# input-device.net
KiCad netlist of a schematic drawn in EAGLE
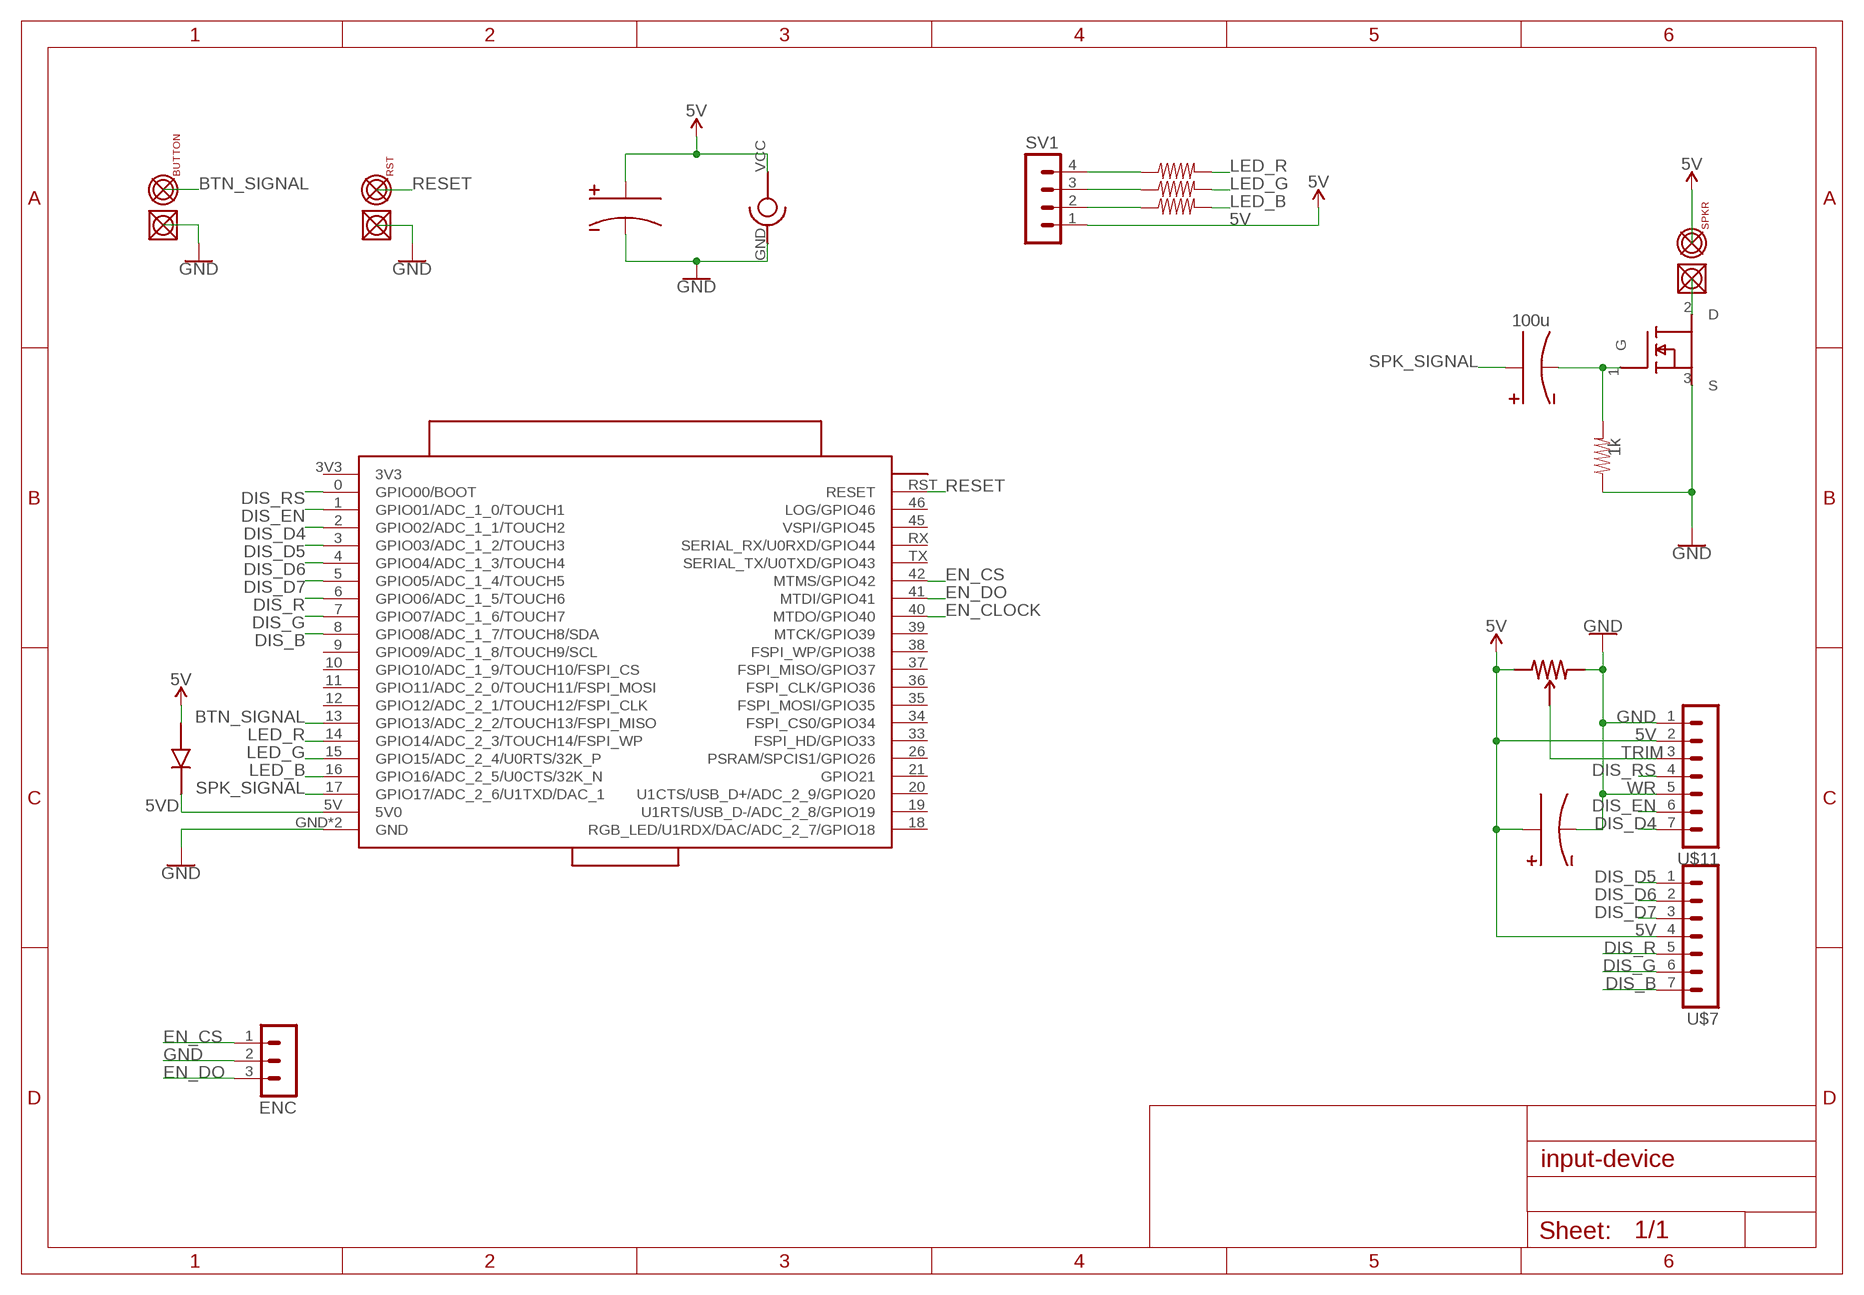
[diagram p0: schematic, sheet 1]

(export (version "E")
  (design (tool "Eeschema 10.0.6"))
  (components
    (comp (ref "BUTTON")
      (value "PIN-HEADER-02X1GROUND")
      (footprint "eagle-import:02X1-PAD-2.54PITCH-MASK-NAME")
      (libsource (lib "eagle-import") (part "PIN-HEADER-02X1GROUND"))
    )
    (comp (ref "ENC")
      (value "PIN-HEADER-03X1THRU-254")
      (footprint "eagle-import:MA03-1")
      (libsource (lib "eagle-import") (part "PIN-HEADER-03X1THRU-254"))
    )
    (comp (ref "IRL540NPBF")
      (value "MOSFET-N-IRL540NPBFBENDED-SHORTEST")
      (footprint "eagle-import:TO220AH-SHORTEST-BEND")
      (libsource (lib "eagle-import") (part "MOSFET-N-IRL540NPBFBENDED-SHORTEST"))
    )
    (comp (ref "R")
      (value "1k")
      (footprint "eagle-import:RESISTOR-THRU-1_4")
      (fields (field (name "R1") "1k"))
      (libsource (lib "eagle-import") (part "RESISTOR"))
    )
    (comp (ref "RST")
      (value "PIN-HEADER-02X1GROUND")
      (footprint "eagle-import:02X1-PAD-2.54PITCH-MASK-NAME")
      (libsource (lib "eagle-import") (part "PIN-HEADER-02X1GROUND"))
    )
    (comp (ref "SPKR")
      (value "PIN-HEADER-02X1GROUND")
      (footprint "eagle-import:02X1-PAD-2.54PITCH-MASK-NAME")
      (libsource (lib "eagle-import") (part "PIN-HEADER-02X1GROUND"))
    )
    (comp (ref "SV1")
      (value "PIN-HEADER-04X01")
      (footprint "eagle-import:MA04-1")
      (libsource (lib "eagle-import") (part "PIN-HEADER-04X01"))
    )
    (comp (ref "U$1")
      (value "RESISTOR")
      (footprint "eagle-import:RESISTOR-THRU-1_4")
      (libsource (lib "eagle-import") (part "RESISTOR"))
    )
    (comp (ref "U$2")
      (value "POWER-JACK")
      (footprint "eagle-import:JACK-5.5X2.1-THRU")
      (libsource (lib "eagle-import") (part "POWER-JACK"))
    )
    (comp (ref "U$3")
      (value "ESP32-S2-SAOLA-1")
      (footprint "eagle-import:ESP32-S2-SAOLA-1")
      (libsource (lib "eagle-import") (part "ESP32-S2-SAOLA-1"))
    )
    (comp (ref "U$4")
      (value "RESISTOR")
      (footprint "eagle-import:RESISTOR-THRU-1_4")
      (libsource (lib "eagle-import") (part "RESISTOR"))
    )
    (comp (ref "U$5")
      (value "100")
      (footprint "eagle-import:RESISTOR-THRU-1_4")
      (libsource (lib "eagle-import") (part "RESISTOR"))
    )
    (comp (ref "U$6")
      (value "CAPACITOR-POLARIZEDCAP-DIAM-8.3MM-H-12MM-BENT")
      (footprint "eagle-import:CAP-DIAM-8.3MM-H-12MM-BENT")
      (libsource (lib "eagle-import") (part "CAPACITOR-POLARIZEDCAP-DIAM-8.3MM-H-12MM-BENT"))
    )
    (comp (ref "U$7")
      (value "PIN-HEADER-07X1")
      (footprint "eagle-import:MA07-1")
      (libsource (lib "eagle-import") (part "PIN-HEADER-07X1"))
    )
    (comp (ref "U$8")
      (value "DIODE")
      (footprint "eagle-import:DIODE")
      (libsource (lib "eagle-import") (part "DIODE"))
    )
    (comp (ref "U$9")
      (value "TRIMMER")
      (footprint "eagle-import:TRIMMER-PLASTIC-BLUE-9MM-2,54")
      (libsource (lib "eagle-import") (part "TRIMMER"))
    )
    (comp (ref "U$11")
      (value "PIN-HEADER-07X1")
      (footprint "eagle-import:MA07-1")
      (libsource (lib "eagle-import") (part "PIN-HEADER-07X1"))
    )
    (comp (ref "U$13")
      (value "CAPACITOR-POLARIZEDCAP-DIAM-8.3MM-H-12MM-BENT")
      (footprint "eagle-import:CAP-DIAM-8.3MM-H-12MM-BENT")
      (libsource (lib "eagle-import") (part "CAPACITOR-POLARIZEDCAP-DIAM-8.3MM-H-12MM-BENT"))
    )
    (comp (ref "U$14")
      (value "100u")
      (footprint "eagle-import:CAP-DIAM-6.5MM-H-11.3MM-BENT-FLIP")
      (fields (field (name "C1") "100u"))
      (libsource (lib "eagle-import") (part "CAPACITOR-POLARIZEDCAP-DIAM-6.5MM-H11.3MM-BENT-FLIP"))
    )
  )
  (nets
    (net (code "1") (name "/5VD") (class "Default")
      (node (ref "U$3") (pin "5V") (pinfunction "5V0_5V") (pintype "bidirectional"))
      (node (ref "U$8") (pin "OUT") (pinfunction "OUT_OUT") (pintype "bidirectional"))
    )
    (net (code "2") (name "/BTN_SIGNAL") (class "Default")
      (node (ref "BUTTON") (pin "1") (pinfunction "1_1") (pintype "bidirectional"))
      (node (ref "U$3") (pin "13") (pinfunction "GPIO13/ADC_2_2/TOUCH13/FSPI_MISO_13") (pintype "bidirectional"))
    )
    (net (code "3") (name "/DIS_B") (class "Default")
      (node (ref "U$3") (pin "8") (pinfunction "GPIO08/ADC_1_7/TOUCH8/SDA_8") (pintype "bidirectional"))
      (node (ref "U$7") (pin "7") (pinfunction "7_7") (pintype "passive"))
    )
    (net (code "4") (name "/DIS_D4") (class "Default")
      (node (ref "U$11") (pin "7") (pinfunction "7_7") (pintype "passive"))
      (node (ref "U$3") (pin "2") (pinfunction "GPIO02/ADC_1_1/TOUCH2_2") (pintype "bidirectional"))
    )
    (net (code "5") (name "/DIS_D5") (class "Default")
      (node (ref "U$3") (pin "3") (pinfunction "GPIO03/ADC_1_2/TOUCH3_3") (pintype "bidirectional"))
      (node (ref "U$7") (pin "1") (pinfunction "1_1") (pintype "passive"))
    )
    (net (code "6") (name "/DIS_D6") (class "Default")
      (node (ref "U$3") (pin "4") (pinfunction "GPIO04/ADC_1_3/TOUCH4_4") (pintype "bidirectional"))
      (node (ref "U$7") (pin "2") (pinfunction "2_2") (pintype "passive"))
    )
    (net (code "7") (name "/DIS_D7") (class "Default")
      (node (ref "U$3") (pin "5") (pinfunction "GPIO05/ADC_1_4/TOUCH5_5") (pintype "bidirectional"))
      (node (ref "U$7") (pin "3") (pinfunction "3_3") (pintype "passive"))
    )
    (net (code "8") (name "/DIS_EN") (class "Default")
      (node (ref "U$11") (pin "6") (pinfunction "6_6") (pintype "passive"))
      (node (ref "U$3") (pin "1") (pinfunction "GPIO01/ADC_1_0/TOUCH1_1") (pintype "bidirectional"))
    )
    (net (code "9") (name "/DIS_G") (class "Default")
      (node (ref "U$3") (pin "7") (pinfunction "GPIO07/ADC_1_6/TOUCH7_7") (pintype "bidirectional"))
      (node (ref "U$7") (pin "6") (pinfunction "6_6") (pintype "passive"))
    )
    (net (code "10") (name "/DIS_R") (class "Default")
      (node (ref "U$3") (pin "6") (pinfunction "GPIO06/ADC_1_5/TOUCH6_6") (pintype "bidirectional"))
      (node (ref "U$7") (pin "5") (pinfunction "5_5") (pintype "passive"))
    )
    (net (code "11") (name "/DIS_RS") (class "Default")
      (node (ref "U$11") (pin "4") (pinfunction "4_4") (pintype "passive"))
      (node (ref "U$3") (pin "0") (pinfunction "GPIO00/BOOT_0") (pintype "bidirectional"))
    )
    (net (code "12") (name "/EN_CLOCK") (class "Default")
      (node (ref "U$3") (pin "40") (pinfunction "MTDO/GPIO40_40") (pintype "bidirectional"))
    )
    (net (code "13") (name "/EN_CS") (class "Default")
      (node (ref "ENC") (pin "1") (pinfunction "1_1") (pintype "passive"))
      (node (ref "U$3") (pin "42") (pinfunction "MTMS/GPIO42_42") (pintype "bidirectional"))
    )
    (net (code "14") (name "/EN_DO") (class "Default")
      (node (ref "ENC") (pin "3") (pinfunction "3_3") (pintype "passive"))
      (node (ref "U$3") (pin "41") (pinfunction "MTDI/GPIO41_41") (pintype "bidirectional"))
    )
    (net (code "15") (name "/LED_B") (class "Default")
      (node (ref "U$3") (pin "16") (pinfunction "GPIO16/ADC_2_5/U0CTS/32K_N_16") (pintype "bidirectional"))
      (node (ref "U$5") (pin "2") (pinfunction "P$2_2") (pintype "bidirectional"))
    )
    (net (code "16") (name "/LED_G") (class "Default")
      (node (ref "U$3") (pin "15") (pinfunction "GPIO15/ADC_2_4/U0RTS/32K_P_15") (pintype "bidirectional"))
      (node (ref "U$4") (pin "2") (pinfunction "P$2_2") (pintype "bidirectional"))
    )
    (net (code "17") (name "/LED_R") (class "Default")
      (node (ref "U$1") (pin "2") (pinfunction "P$2_2") (pintype "bidirectional"))
      (node (ref "U$3") (pin "14") (pinfunction "GPIO14/ADC_2_3/TOUCH14/FSPI_WP_14") (pintype "bidirectional"))
    )
    (net (code "18") (name "/RESET") (class "Default")
      (node (ref "RST") (pin "1") (pinfunction "1_1") (pintype "bidirectional"))
      (node (ref "U$3") (pin "RST") (pinfunction "RESET_RST") (pintype "bidirectional"))
    )
    (net (code "19") (name "/SPK_SIGNAL") (class "Default")
      (node (ref "U$14") (pin "VCC") (pinfunction "VCC_VCC") (pintype "bidirectional"))
      (node (ref "U$3") (pin "17") (pinfunction "GPIO17/ADC_2_6/U1TXD/DAC_1_17") (pintype "bidirectional"))
    )
    (net (code "20") (name "/TRIM") (class "Default")
      (node (ref "U$11") (pin "3") (pinfunction "3_3") (pintype "passive"))
      (node (ref "U$9") (pin "C") (pinfunction "C_C") (pintype "bidirectional"))
    )
    (net (code "21") (name "5V") (class "Default")
      (node (ref "SPKR") (pin "1") (pinfunction "1_1") (pintype "bidirectional"))
      (node (ref "SV1") (pin "1") (pinfunction "1_1") (pintype "passive"))
      (node (ref "U$11") (pin "2") (pinfunction "2_2") (pintype "passive"))
      (node (ref "U$13") (pin "VCC") (pinfunction "VCC_VCC") (pintype "bidirectional"))
      (node (ref "U$2") (pin "VCC") (pinfunction "VCC_VCC") (pintype "bidirectional"))
      (node (ref "U$6") (pin "VCC") (pinfunction "VCC_VCC") (pintype "bidirectional"))
      (node (ref "U$7") (pin "4") (pinfunction "4_4") (pintype "passive"))
      (node (ref "U$8") (pin "IN") (pinfunction "IN_IN") (pintype "bidirectional"))
      (node (ref "U$9") (pin "A") (pinfunction "A_A") (pintype "bidirectional"))
    )
    (net (code "22") (name "GND") (class "Default")
      (node (ref "BUTTON") (pin "2") (pinfunction "2_2") (pintype "bidirectional"))
      (node (ref "ENC") (pin "2") (pinfunction "2_2") (pintype "passive"))
      (node (ref "IRL540NPBF") (pin "3") (pinfunction "S_3") (pintype "bidirectional"))
      (node (ref "R") (pin "1") (pinfunction "P$1_1") (pintype "bidirectional"))
      (node (ref "RST") (pin "2") (pinfunction "2_2") (pintype "bidirectional"))
      (node (ref "U$11") (pin "1") (pinfunction "1_1") (pintype "passive"))
      (node (ref "U$11") (pin "5") (pinfunction "5_5") (pintype "passive"))
      (node (ref "U$13") (pin "GND") (pinfunction "GND_GND") (pintype "bidirectional"))
      (node (ref "U$2") (pin "GND") (pinfunction "GND_GND") (pintype "bidirectional"))
      (node (ref "U$3") (pin "GND") (pinfunction "GND_GND") (pintype "bidirectional"))
      (node (ref "U$3") (pin "GND2") (pinfunction "GND_GND2") (pintype "bidirectional"))
      (node (ref "U$6") (pin "GND") (pinfunction "GND_GND") (pintype "bidirectional"))
      (node (ref "U$9") (pin "B") (pinfunction "B_B") (pintype "bidirectional"))
    )
    (net (code "23") (name "Net-(IRL540NPBF-D)") (class "Default")
      (node (ref "IRL540NPBF") (pin "2") (pinfunction "D_2") (pintype "bidirectional"))
      (node (ref "SPKR") (pin "2") (pinfunction "2_2") (pintype "bidirectional"))
    )
    (net (code "24") (name "Net-(IRL540NPBF-G)") (class "Default")
      (node (ref "IRL540NPBF") (pin "1") (pinfunction "G_1") (pintype "bidirectional"))
      (node (ref "R") (pin "2") (pinfunction "P$2_2") (pintype "bidirectional"))
      (node (ref "U$14") (pin "GND") (pinfunction "GND_GND") (pintype "bidirectional"))
    )
    (net (code "25") (name "Net-(U$1-P$1)") (class "Default")
      (node (ref "SV1") (pin "4") (pinfunction "4_4") (pintype "passive"))
      (node (ref "U$1") (pin "1") (pinfunction "P$1_1") (pintype "bidirectional"))
    )
    (net (code "26") (name "Net-(U$4-P$1)") (class "Default")
      (node (ref "SV1") (pin "3") (pinfunction "3_3") (pintype "passive"))
      (node (ref "U$4") (pin "1") (pinfunction "P$1_1") (pintype "bidirectional"))
    )
    (net (code "27") (name "Net-(U$5-P$1)") (class "Default")
      (node (ref "SV1") (pin "2") (pinfunction "2_2") (pintype "passive"))
      (node (ref "U$5") (pin "1") (pinfunction "P$1_1") (pintype "bidirectional"))
    )
    (net (code "28") (name "unconnected-(U$3-FSPI_CLK{slash}GPIO36-Pad36)") (class "Default")
      (node (ref "U$3") (pin "36") (pinfunction "FSPI_CLK/GPIO36_36") (pintype "bidirectional"))
    )
    (net (code "29") (name "unconnected-(U$3-FSPI_CS0{slash}GPIO34-Pad34)") (class "Default")
      (node (ref "U$3") (pin "34") (pinfunction "FSPI_CS0/GPIO34_34") (pintype "bidirectional"))
    )
    (net (code "30") (name "unconnected-(U$3-FSPI_HD{slash}GPIO33-Pad33)") (class "Default")
      (node (ref "U$3") (pin "33") (pinfunction "FSPI_HD/GPIO33_33") (pintype "bidirectional"))
    )
    (net (code "31") (name "unconnected-(U$3-FSPI_MISO{slash}GPIO37-Pad37)") (class "Default")
      (node (ref "U$3") (pin "37") (pinfunction "FSPI_MISO/GPIO37_37") (pintype "bidirectional"))
    )
    (net (code "32") (name "unconnected-(U$3-FSPI_MOSI{slash}GPIO35-Pad35)") (class "Default")
      (node (ref "U$3") (pin "35") (pinfunction "FSPI_MOSI/GPIO35_35") (pintype "bidirectional"))
    )
    (net (code "33") (name "unconnected-(U$3-FSPI_WP{slash}GPIO38-Pad38)") (class "Default")
      (node (ref "U$3") (pin "38") (pinfunction "FSPI_WP/GPIO38_38") (pintype "bidirectional"))
    )
    (net (code "34") (name "unconnected-(U$3-GPIO09{slash}ADC_1_8{slash}TOUCH9{slash}SCL-Pad9)") (class "Default")
      (node (ref "U$3") (pin "9") (pinfunction "GPIO09/ADC_1_8/TOUCH9/SCL_9") (pintype "bidirectional"))
    )
    (net (code "35") (name "unconnected-(U$3-GPIO10{slash}ADC_1_9{slash}TOUCH10{slash}FSPI_CS-Pad10)") (class "Default")
      (node (ref "U$3") (pin "10") (pinfunction "GPIO10/ADC_1_9/TOUCH10/FSPI_CS_10") (pintype "bidirectional"))
    )
    (net (code "36") (name "unconnected-(U$3-GPIO11{slash}ADC_2_0{slash}TOUCH11{slash}FSPI_MOSI-Pad11)") (class "Default")
      (node (ref "U$3") (pin "11") (pinfunction "GPIO11/ADC_2_0/TOUCH11/FSPI_MOSI_11") (pintype "bidirectional"))
    )
    (net (code "37") (name "unconnected-(U$3-GPIO12{slash}ADC_2_1{slash}TOUCH12{slash}FSPI_CLK-Pad12)") (class "Default")
      (node (ref "U$3") (pin "12") (pinfunction "GPIO12/ADC_2_1/TOUCH12/FSPI_CLK_12") (pintype "bidirectional"))
    )
    (net (code "38") (name "unconnected-(U$3-GPIO21-Pad21)") (class "Default")
      (node (ref "U$3") (pin "21") (pinfunction "GPIO21_21") (pintype "bidirectional"))
    )
    (net (code "39") (name "unconnected-(U$3-LOG{slash}GPIO46-Pad46)") (class "Default")
      (node (ref "U$3") (pin "46") (pinfunction "LOG/GPIO46_46") (pintype "bidirectional"))
    )
    (net (code "40") (name "unconnected-(U$3-MTCK{slash}GPIO39-Pad39)") (class "Default")
      (node (ref "U$3") (pin "39") (pinfunction "MTCK/GPIO39_39") (pintype "bidirectional"))
    )
    (net (code "41") (name "unconnected-(U$3-PSRAM{slash}SPCIS1{slash}GPIO26-Pad26)") (class "Default")
      (node (ref "U$3") (pin "26") (pinfunction "PSRAM/SPCIS1/GPIO26_26") (pintype "bidirectional"))
    )
    (net (code "42") (name "unconnected-(U$3-Pad3V3)") (class "Default")
      (node (ref "U$3") (pin "3V3") (pinfunction "3V3_3V3") (pintype "bidirectional"))
    )
    (net (code "43") (name "unconnected-(U$3-RGB_LED{slash}U1RDX{slash}DAC{slash}ADC_2_7{slash}GPIO18-Pad18)") (class "Default")
      (node (ref "U$3") (pin "18") (pinfunction "RGB_LED/U1RDX/DAC/ADC_2_7/GPIO18_18") (pintype "bidirectional"))
    )
    (net (code "44") (name "unconnected-(U$3-SERIAL_RX{slash}U0RXD{slash}GPIO44-PadRX)") (class "Default")
      (node (ref "U$3") (pin "RX") (pinfunction "SERIAL_RX/U0RXD/GPIO44_RX") (pintype "bidirectional"))
    )
    (net (code "45") (name "unconnected-(U$3-SERIAL_TX{slash}U0TXD{slash}GPIO43-PadTX)") (class "Default")
      (node (ref "U$3") (pin "TX") (pinfunction "SERIAL_TX/U0TXD/GPIO43_TX") (pintype "bidirectional"))
    )
    (net (code "46") (name "unconnected-(U$3-U1CTS{slash}USB_D+{slash}ADC_2_9{slash}GPIO20-Pad20)") (class "Default")
      (node (ref "U$3") (pin "20") (pinfunction "U1CTS/USB_D+/ADC_2_9/GPIO20_20") (pintype "bidirectional"))
    )
    (net (code "47") (name "unconnected-(U$3-U1RTS{slash}USB_D-{slash}ADC_2_8{slash}GPIO19-Pad19)") (class "Default")
      (node (ref "U$3") (pin "19") (pinfunction "U1RTS/USB_D-/ADC_2_8/GPIO19_19") (pintype "bidirectional"))
    )
    (net (code "48") (name "unconnected-(U$3-VSPI{slash}GPIO45-Pad45)") (class "Default")
      (node (ref "U$3") (pin "45") (pinfunction "VSPI/GPIO45_45") (pintype "bidirectional"))
    )
  )
)
